# USB-RS232_Schematic.net
KiCad netlist of a schematic drawn in Altium Designer
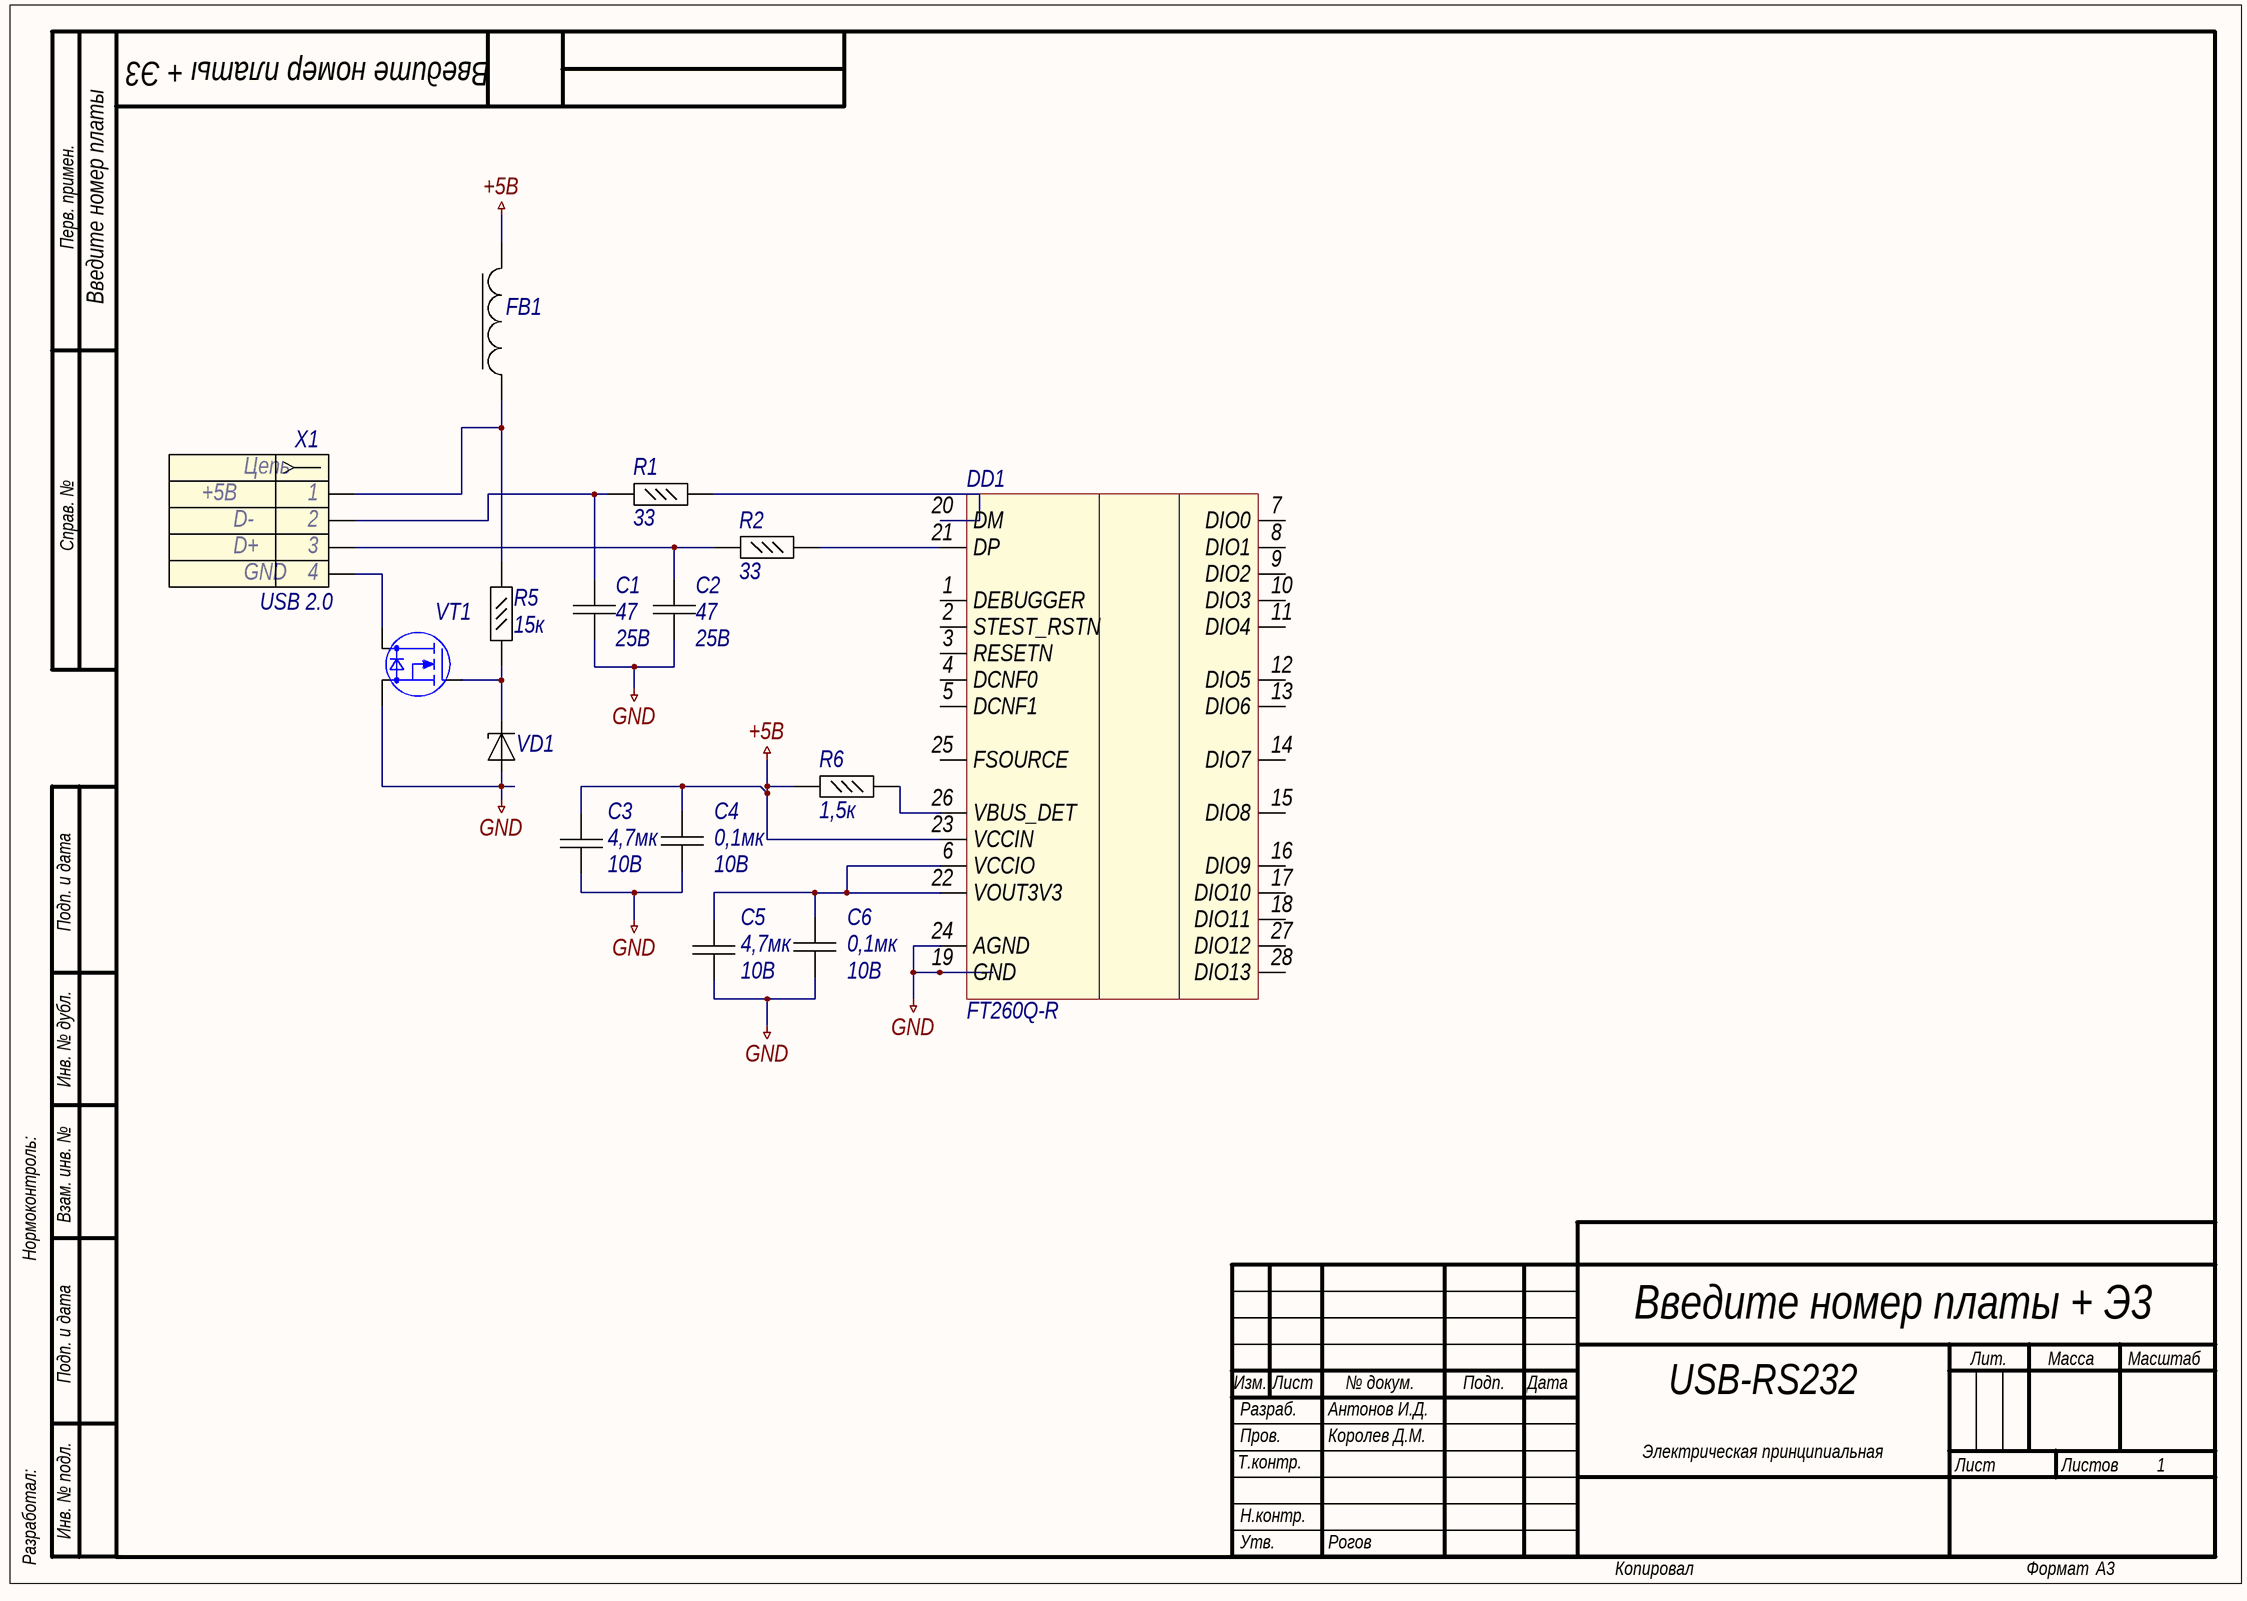
[diagram p0: USB-RS232_Schematic.SchDoc]

(export (version "E")
  (design (tool "Eeschema 10.0.6"))
  (components
    (comp (ref "C1")
      (value "Capacitor")
      (footprint "CH0201C")
      (fields (field (name "VOLTAGE") "25В") (field (name "CAPACITANCE") "47"))
      (libsource (lib "GOST_Capacitors") (part "Capacitor"))
    )
    (comp (ref "C2")
      (value "Capacitor")
      (footprint "CH0201C")
      (fields (field (name "VOLTAGE") "25В") (field (name "CAPACITANCE") "47"))
      (libsource (lib "GOST_Capacitors") (part "Capacitor"))
    )
    (comp (ref "C3")
      (value "Capacitor")
      (footprint "CH0402C")
      (fields (field (name "VOLTAGE") "10В") (field (name "CAPACITANCE") "4,7мк"))
      (libsource (lib "GOST_Capacitors") (part "Capacitor"))
    )
    (comp (ref "C4")
      (value "Capacitor")
      (footprint "CH0402C")
      (fields (field (name "VOLTAGE") "10В") (field (name "CAPACITANCE") "0,1мк"))
      (libsource (lib "GOST_Capacitors") (part "Capacitor"))
    )
    (comp (ref "C5")
      (value "Capacitor")
      (footprint "CH0402C")
      (fields (field (name "VOLTAGE") "10В") (field (name "CAPACITANCE") "4,7мк"))
      (libsource (lib "GOST_Capacitors") (part "Capacitor"))
    )
    (comp (ref "C6")
      (value "Capacitor")
      (footprint "CH0402C")
      (fields (field (name "VOLTAGE") "10В") (field (name "CAPACITANCE") "0,1мк"))
      (libsource (lib "GOST_Capacitors") (part "Capacitor"))
    )
    (comp (ref "DD1")
      (value "FT260Q-R")
      (footprint "FT260-Q")
      (description "IC BRIDGE USB TO UART/I2C 28WQFN")
      (libsource (lib "GOST_lib_devices") (part "FT260Q-R"))
    )
    (comp (ref "FB1")
      (value "Ferrite bead")
      (footprint "CH0805F")
      (libsource (lib "GOST_Inductors") (part "Ferrite bead"))
    )
    (comp (ref "R1")
      (value "Res_0.05")
      (footprint "CH0201R")
      (fields (field (name "RESISTANCE") "33"))
      (libsource (lib "GOST_Resistors") (part "Res_0.05"))
    )
    (comp (ref "R2")
      (value "Res_0.05")
      (footprint "CH0201R")
      (fields (field (name "RESISTANCE") "33"))
      (libsource (lib "GOST_Resistors") (part "Res_0.05"))
    )
    (comp (ref "R5")
      (value "Res_0.05")
      (footprint "CH0201R")
      (fields (field (name "RESISTANCE") "15к"))
      (libsource (lib "GOST_Resistors") (part "Res_0.05"))
    )
    (comp (ref "R6")
      (value "Res_0.05")
      (footprint "CH0201R")
      (fields (field (name "RESISTANCE") "1,5к"))
      (libsource (lib "GOST_Resistors") (part "Res_0.05"))
    )
    (comp (ref "VD1")
      (value "BZT52H-C7V5,115")
      (footprint "standard:SOD123F")
      (fields (field (name "MANUFACTURER") "Nexperia"))
      (libsource (lib "Diods") (part "Diod Zener"))
    )
    (comp (ref "VT1")
      (value "N-MOSFET")
      (footprint "DMP1200UFR47")
      (fields
        (field (name "PART NUMBER") "DMN1045UFR4-7")
        (field (name "MANUFACTURER") "Diodes Incorporated")
      )
      (libsource (lib "MOP44") (part "N-MOSFET"))
    )
    (comp (ref "X1")
      (value "USB 2.0")
      (footprint "Integrated_Library:USB")
      (description "USB")
      (fields (field (name "MANUFACTURER") "TE Connectivity") (field (name "VCC") "+5В"))
      (libsource (lib "Connectors") (part "USB-A"))
    )
  )
  (nets
    (net (code "1") (name "+5В") (class "Default")
      (node (ref "C3") (pin "11") (pinfunction "C1+_11") (pintype "power_in"))
      (node (ref "C4") (pin "11") (pinfunction "C1+_11") (pintype "power_in"))
      (node (ref "DD1") (pin "23") (pinfunction "VCCIN_23") (pintype "passive"))
      (node (ref "FB1") (pin "14") (pinfunction "14_14") (pintype "power_in"))
      (node (ref "R6") (pin "9") (pinfunction "C1-_9") (pintype "power_in"))
    )
    (net (code "2") (name "GND") (class "Default")
      (node (ref "C1") (pin "11") (pinfunction "C1+_11") (pintype "power_in"))
      (node (ref "C2") (pin "11") (pinfunction "C1+_11") (pintype "power_in"))
      (node (ref "C3") (pin "11") (pinfunction "C1-_11") (pintype "power_in"))
      (node (ref "C4") (pin "11") (pinfunction "C1-_11") (pintype "power_in"))
      (node (ref "C5") (pin "11") (pinfunction "C1-_11") (pintype "power_in"))
      (node (ref "C6") (pin "11") (pinfunction "C1-_11") (pintype "power_in"))
      (node (ref "DD1") (pin "19") (pinfunction "GND_19") (pintype "passive"))
      (node (ref "DD1") (pin "24") (pinfunction "AGND_24") (pintype "passive"))
      (node (ref "VD1") (pin "1") (pinfunction "A_1") (pintype "passive"))
      (node (ref "VT1") (pin "2") (pinfunction "S_2") (pintype "passive"))
    )
    (net (code "3") (name "Net-(C1-C1-)") (class "Default")
      (node (ref "C1") (pin "11") (pinfunction "C1-_11") (pintype "power_in"))
      (node (ref "R1") (pin "9") (pinfunction "C1-_9") (pintype "power_in"))
      (node (ref "X1") (pin "2") (pinfunction "2_2") (pintype "passive"))
    )
    (net (code "4") (name "Net-(C2-C1-)") (class "Default")
      (node (ref "C2") (pin "11") (pinfunction "C1-_11") (pintype "power_in"))
      (node (ref "R2") (pin "9") (pinfunction "C1-_9") (pintype "power_in"))
      (node (ref "X1") (pin "3") (pinfunction "3_3") (pintype "passive"))
    )
    (net (code "5") (name "Net-(C5-C1+)") (class "Default")
      (node (ref "C5") (pin "11") (pinfunction "C1+_11") (pintype "power_in"))
      (node (ref "C6") (pin "11") (pinfunction "C1+_11") (pintype "power_in"))
      (node (ref "DD1") (pin "22") (pinfunction "VOUT3V3_22") (pintype "passive"))
      (node (ref "DD1") (pin "6") (pinfunction "VCCIO_6") (pintype "passive"))
    )
    (net (code "6") (name "Net-(DD1-DM)") (class "Default")
      (node (ref "DD1") (pin "20") (pinfunction "DM_20") (pintype "passive"))
      (node (ref "R1") (pin "10") (pinfunction "C1-_10") (pintype "power_in"))
    )
    (net (code "7") (name "Net-(DD1-DP)") (class "Default")
      (node (ref "DD1") (pin "21") (pinfunction "DP_21") (pintype "passive"))
      (node (ref "R2") (pin "10") (pinfunction "C1-_10") (pintype "power_in"))
    )
    (net (code "8") (name "Net-(DD1-VBUS_DET)") (class "Default")
      (node (ref "DD1") (pin "26") (pinfunction "VBUS_DET_26") (pintype "passive"))
      (node (ref "R6") (pin "10") (pinfunction "C1-_10") (pintype "power_in"))
    )
    (net (code "9") (name "Net-(FB1-C1-)") (class "Default")
      (node (ref "FB1") (pin "13") (pinfunction "C1-_13") (pintype "power_in"))
      (node (ref "R5") (pin "10") (pinfunction "C1-_10") (pintype "power_in"))
      (node (ref "X1") (pin "1") (pintype "passive"))
    )
    (net (code "10") (name "Net-(VD1-C)") (class "Default")
      (node (ref "R5") (pin "9") (pinfunction "C1-_9") (pintype "power_in"))
      (node (ref "VD1") (pin "2") (pinfunction "C_2") (pintype "passive"))
      (node (ref "VT1") (pin "1") (pinfunction "G_1") (pintype "passive"))
    )
    (net (code "11") (name "Net-(VT1-D)") (class "Default")
      (node (ref "VT1") (pin "3") (pinfunction "D_3") (pintype "passive"))
      (node (ref "X1") (pin "4") (pinfunction "4_4") (pintype "passive"))
    )
    (net (code "12") (name "unconnected-(DD1-DCNF0-Pad4)") (class "Default")
      (node (ref "DD1") (pin "4") (pinfunction "DCNF0_4") (pintype "passive"))
    )
    (net (code "13") (name "unconnected-(DD1-DCNF1-Pad5)") (class "Default")
      (node (ref "DD1") (pin "5") (pinfunction "DCNF1_5") (pintype "passive"))
    )
    (net (code "14") (name "unconnected-(DD1-DEBUGGER-Pad1)") (class "Default")
      (node (ref "DD1") (pin "1") (pinfunction "DEBUGGER_1") (pintype "passive"))
    )
    (net (code "15") (name "unconnected-(DD1-DIO0-Pad7)") (class "Default")
      (node (ref "DD1") (pin "7") (pinfunction "DIO0_7") (pintype "passive"))
    )
    (net (code "16") (name "unconnected-(DD1-DIO1-Pad8)") (class "Default")
      (node (ref "DD1") (pin "8") (pinfunction "DIO1_8") (pintype "passive"))
    )
    (net (code "17") (name "unconnected-(DD1-DIO2-Pad9)") (class "Default")
      (node (ref "DD1") (pin "9") (pinfunction "DIO2_9") (pintype "passive"))
    )
    (net (code "18") (name "unconnected-(DD1-DIO3-Pad10)") (class "Default")
      (node (ref "DD1") (pin "10") (pinfunction "DIO3_10") (pintype "passive"))
    )
    (net (code "19") (name "unconnected-(DD1-DIO4-Pad11)") (class "Default")
      (node (ref "DD1") (pin "11") (pinfunction "DIO4_11") (pintype "passive"))
    )
    (net (code "20") (name "unconnected-(DD1-DIO5-Pad12)") (class "Default")
      (node (ref "DD1") (pin "12") (pinfunction "DIO5_12") (pintype "passive"))
    )
    (net (code "21") (name "unconnected-(DD1-DIO6-Pad13)") (class "Default")
      (node (ref "DD1") (pin "13") (pinfunction "DIO6_13") (pintype "passive"))
    )
    (net (code "22") (name "unconnected-(DD1-DIO7-Pad14)") (class "Default")
      (node (ref "DD1") (pin "14") (pinfunction "DIO7_14") (pintype "passive"))
    )
    (net (code "23") (name "unconnected-(DD1-DIO8-Pad15)") (class "Default")
      (node (ref "DD1") (pin "15") (pinfunction "DIO8_15") (pintype "passive"))
    )
    (net (code "24") (name "unconnected-(DD1-DIO9-Pad16)") (class "Default")
      (node (ref "DD1") (pin "16") (pinfunction "DIO9_16") (pintype "passive"))
    )
    (net (code "25") (name "unconnected-(DD1-DIO10-Pad17)") (class "Default")
      (node (ref "DD1") (pin "17") (pinfunction "DIO10_17") (pintype "passive"))
    )
    (net (code "26") (name "unconnected-(DD1-DIO11-Pad18)") (class "Default")
      (node (ref "DD1") (pin "18") (pinfunction "DIO11_18") (pintype "passive"))
    )
    (net (code "27") (name "unconnected-(DD1-DIO12-Pad27)") (class "Default")
      (node (ref "DD1") (pin "27") (pinfunction "DIO12_27") (pintype "passive"))
    )
    (net (code "28") (name "unconnected-(DD1-DIO13-Pad28)") (class "Default")
      (node (ref "DD1") (pin "28") (pinfunction "DIO13_28") (pintype "passive"))
    )
    (net (code "29") (name "unconnected-(DD1-FSOURCE-Pad25)") (class "Default")
      (node (ref "DD1") (pin "25") (pinfunction "FSOURCE_25") (pintype "passive"))
    )
    (net (code "30") (name "unconnected-(DD1-RESETN-Pad3)") (class "Default")
      (node (ref "DD1") (pin "3") (pinfunction "RESETN_3") (pintype "passive"))
    )
    (net (code "31") (name "unconnected-(DD1-STEST_RSTN-Pad2)") (class "Default")
      (node (ref "DD1") (pin "2") (pinfunction "STEST_RSTN_2") (pintype "passive"))
    )
  )
)
